# ProPrj___2025-12-10.net
KiCad netlist of a schematic drawn in EasyEDA Pro
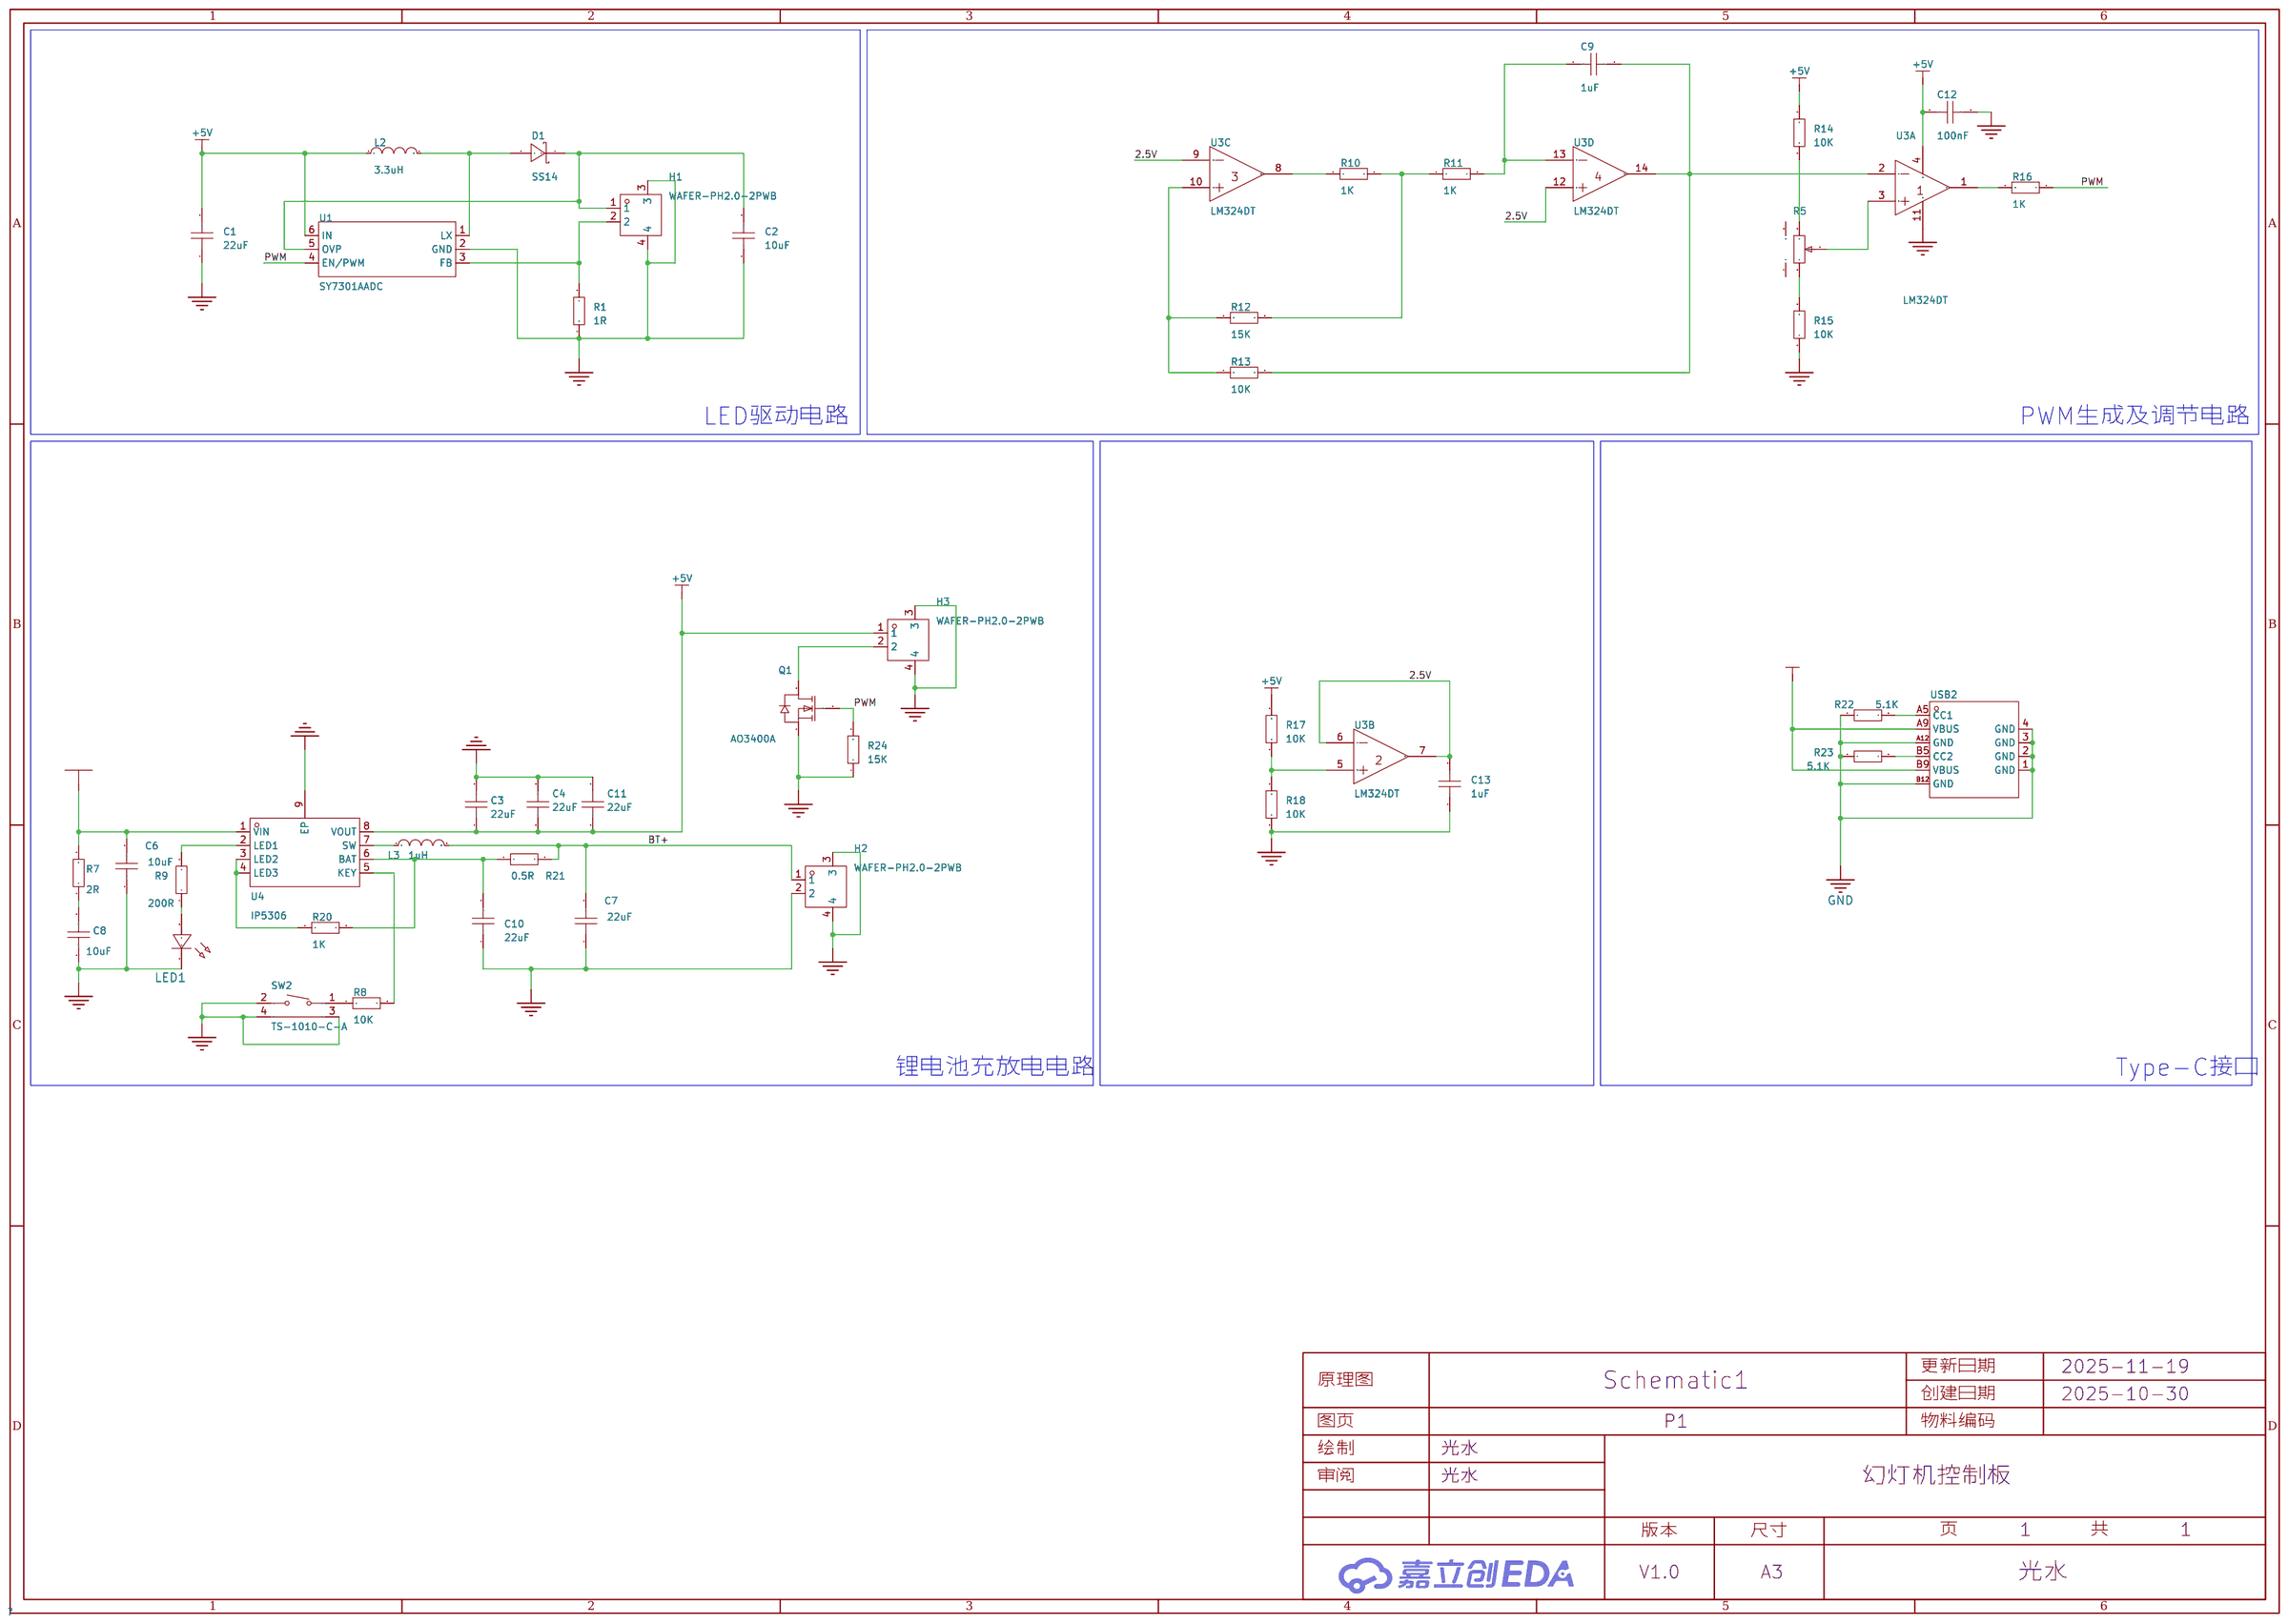
[diagram p0: schematic sheet]

(export (version "E")
  (design (tool "Eeschema 10.0.6"))
  (components
    (comp (ref "C1")
      (value "22uF")
      (footprint "easyedapro:C1206")
      (libsource (lib "easyedapro") (part "CapAcitance"))
    )
    (comp (ref "C2")
      (value "10uF")
      (footprint "easyedapro:C1206")
      (libsource (lib "easyedapro") (part "CapAcitance"))
    )
    (comp (ref "C3")
      (value "22uF")
      (footprint "easyedapro:C0805")
      (description "容值:100nF;精度:±10%;额定电压:50V;温度系数:X7R;")
      (libsource (lib "easyedapro") (part "C1210X7R475K630NT"))
    )
    (comp (ref "C4")
      (value "22uF")
      (footprint "easyedapro:C0805")
      (description "容值:100nF;精度:±10%;额定电压:50V;温度系数:X7R;")
      (libsource (lib "easyedapro") (part "C1210X7R475K630NT"))
    )
    (comp (ref "C6")
      (value "10uF")
      (footprint "easyedapro:C0805")
      (description "容值:100nF;精度:±10%;额定电压:50V;温度系数:X7R;")
      (libsource (lib "easyedapro") (part "C1210X7R475K630NT"))
    )
    (comp (ref "C7")
      (value "22uF")
      (footprint "easyedapro:C0805")
      (description "容值:100nF;精度:±10%;额定电压:50V;温度系数:X7R;")
      (libsource (lib "easyedapro") (part "C1210X7R475K630NT"))
    )
    (comp (ref "C8")
      (value "10uF")
      (footprint "easyedapro:C0805")
      (description "容值:100nF;精度:±10%;额定电压:50V;温度系数:X7R;")
      (libsource (lib "easyedapro") (part "C1210X7R475K630NT"))
    )
    (comp (ref "C9")
      (value "1uF")
      (footprint "easyedapro:C1206")
      (libsource (lib "easyedapro") (part "CapAcitance"))
    )
    (comp (ref "C10")
      (value "22uF")
      (footprint "easyedapro:C1206")
      (libsource (lib "easyedapro") (part "CapAcitance"))
    )
    (comp (ref "C11")
      (value "22uF")
      (footprint "easyedapro:C0805")
      (description "容值:100nF;精度:±10%;额定电压:50V;温度系数:X7R;")
      (libsource (lib "easyedapro") (part "C1210X7R475K630NT"))
    )
    (comp (ref "C12")
      (value "100nF")
      (footprint "easyedapro:C1206")
      (libsource (lib "easyedapro") (part "CapAcitance"))
    )
    (comp (ref "C13")
      (value "1uF")
      (footprint "easyedapro:C1206")
      (libsource (lib "easyedapro") (part "CapAcitance"))
    )
    (comp (ref "D1")
      (value "SS14")
      (footprint "easyedapro:SMA_L4.2-W2.6-LS5.0-RD_1")
      (description "二极管配置:独立式;正向压降(Vf):550mV@1A;直流反向耐压(Vr):40V;整流电流:1A;")
      (fields (field (name "Manufacturer") "MDD(辰达半导体)"))
      (libsource (lib "easyedapro") (part "SS14"))
    )
    (comp (ref "H1")
      (value "WAFER-PH2.0-2PWB")
      (footprint "easyedapro:CONN-SMD_2P-P2.00_XUNPU_WAFER-PH2.0-2PWB")
      (fields (field (name "Manufacturer") "XUNPU(讯普)"))
      (libsource (lib "easyedapro") (part "WAFER-PH2.0-2PWB"))
    )
    (comp (ref "H2")
      (value "WAFER-PH2.0-2PWB")
      (footprint "easyedapro:CONN-SMD_2P-P2.00_XUNPU_WAFER-PH2.0-2PWB")
      (fields (field (name "Manufacturer") "XUNPU(讯普)"))
      (libsource (lib "easyedapro") (part "WAFER-PH2.0-2PWB"))
    )
    (comp (ref "H3")
      (value "WAFER-PH2.0-2PWB")
      (footprint "easyedapro:CONN-SMD_2P-P2.00_XUNPU_WAFER-PH2.0-2PWB")
      (fields (field (name "Manufacturer") "XUNPU(讯普)"))
      (libsource (lib "easyedapro") (part "WAFER-PH2.0-2PWB"))
    )
    (comp (ref "L2")
      (value "3.3uH")
      (footprint "easyedapro:IND-SMD_L7.3-W6.6")
      (description "电感值:3.3uH;精度:±20%;额定电流:-;饱和电流(Isat):9.5A;类型:-;")
      (fields (field (name "Manufacturer Part") "SMMS0630-3R3M") (field (name "Manufacturer") "SXN(顺翔诺)"))
      (libsource (lib "easyedapro") (part "SMMS0630-3R3M"))
    )
    (comp (ref "L3")
      (value "1uH")
      (footprint "easyedapro:IND-SMD_L6.8-W6.8_SMMS0630")
      (description "电感值:1uH;精度:±20%;额定电流:-;饱和电流(Isat):16A;类型:-;")
      (fields (field (name "Manufacturer Part") "SMMS0630-1R0M") (field (name "Manufacturer") "SXN(顺翔诺)"))
      (libsource (lib "easyedapro") (part "SMMS0630-1R0M"))
    )
    (comp (ref "LED1")
      (value "~")
      (footprint "easyedapro:LED0603-RD_BLUE")
      (libsource (lib "easyedapro") (part "LED_R"))
    )
    (comp (ref "Q1")
      (value "AO3400A")
      (footprint "easyedapro:SOT-23-3_L2.9-W1.3-P1.90-LS2.4-BR")
      (description "数量:-;漏源电压(Vdss):30V;连续漏极电流(Id):-;导通电阻(RDS(on)):48mΩ@2.5V;耗散功率(Pd):-;阈值电压(Vgs(th)):1.45V@250uA;")
      (fields (field (name "Manufacturer") "AOS"))
      (libsource (lib "easyedapro") (part "AO3400A"))
    )
    (comp (ref "R1") (value "1R") (footprint "easyedapro:R1210") (libsource (lib "easyedapro") (part "电阻")))
    (comp (ref "R5")
      (value "RV09AF-40-15K-B10K")
      (footprint "easyedapro:RES-ADJ-TH_RV09")
      (libsource (lib "easyedapro") (part "RV09AF-40-15K-B10K"))
    )
    (comp (ref "R7") (value "2R") (footprint "easyedapro:R0603") (libsource (lib "easyedapro") (part "电阻")))
    (comp (ref "R8") (value "10K") (footprint "easyedapro:R1210") (libsource (lib "easyedapro") (part "电阻")))
    (comp (ref "R9") (value "200R") (footprint "easyedapro:R1210") (libsource (lib "easyedapro") (part "电阻")))
    (comp (ref "R10") (value "1K") (footprint "easyedapro:R1210") (libsource (lib "easyedapro") (part "电阻")))
    (comp (ref "R11") (value "1K") (footprint "easyedapro:R1210") (libsource (lib "easyedapro") (part "电阻")))
    (comp (ref "R12") (value "15K") (footprint "easyedapro:R1210") (libsource (lib "easyedapro") (part "电阻")))
    (comp (ref "R13") (value "10K") (footprint "easyedapro:R1210") (libsource (lib "easyedapro") (part "电阻")))
    (comp (ref "R14") (value "10K") (footprint "easyedapro:R1210") (libsource (lib "easyedapro") (part "电阻")))
    (comp (ref "R15") (value "10K") (footprint "easyedapro:R1210") (libsource (lib "easyedapro") (part "电阻")))
    (comp (ref "R16") (value "1K") (footprint "easyedapro:R1210") (libsource (lib "easyedapro") (part "电阻")))
    (comp (ref "R17") (value "10K") (footprint "easyedapro:R1210") (libsource (lib "easyedapro") (part "电阻")))
    (comp (ref "R18") (value "10K") (footprint "easyedapro:R1210") (libsource (lib "easyedapro") (part "电阻")))
    (comp (ref "R20") (value "1K") (footprint "easyedapro:R1210") (libsource (lib "easyedapro") (part "电阻")))
    (comp (ref "R21")
      (value "0.5R")
      (footprint "easyedapro:R1210")
      (libsource (lib "easyedapro") (part "电阻"))
    )
    (comp (ref "R22")
      (value "5.1K")
      (footprint "easyedapro:R0603")
      (libsource (lib "easyedapro") (part "电阻"))
    )
    (comp (ref "R23")
      (value "5.1K")
      (footprint "easyedapro:R0603")
      (libsource (lib "easyedapro") (part "电阻"))
    )
    (comp (ref "R24") (value "15K") (footprint "easyedapro:R1210") (libsource (lib "easyedapro") (part "电阻")))
    (comp (ref "SW2")
      (value "TS-1010-C-A")
      (footprint "easyedapro:KEY-SMD_TX-1010-X-X")
      (fields (field (name "Manufacturer") "XKB Connectivity(中国星坤)"))
      (libsource (lib "easyedapro") (part "TS-1010-C-A"))
    )
    (comp (ref "U1")
      (value "SY7301AADC")
      (footprint "easyedapro:TSOT-23-6_L2.9-W1.6-P0.95-LS2.8-BR")
      (description "开关频率:800kHz~1.2MHz;通道数:1;调光:PWM；模拟;拓扑结构:升压;")
      (fields (field (name "Manufacturer") "Silergy(矽力杰)"))
      (libsource (lib "easyedapro") (part "SY7301AADC"))
    )
    (comp (ref "U3")
      (value "LM324DT")
      (footprint "easyedapro:SOIC-14_L8.7-W3.9-P1.27-LS6.0-BL")
      (description "放大器数:四路;轨到轨:-;增益带宽积(GBP):1.3MHz;输入失调电压(Vos):5mV;压摆率(SR):20V/us;输入偏置电流(Ib):300nA;")
      (fields (field (name "Manufacturer") "ST(意法半导体)"))
      (libsource (lib "easyedapro") (part "LM324DT"))
    )
    (comp (ref "U4")
      (value "IP5306")
      (footprint "easyedapro:ESOP-8_L4.9-W3.9-P1.27-LS6.0-BL-EP")
      (description "工作电压:4.65V~5.5V;最大充电电流:2.1A;电池类型:锂电池;电池节数:1;")
      (fields (field (name "Manufacturer") "INJOINIC(英集芯)"))
      (libsource (lib "easyedapro") (part "IP5306"))
    )
    (comp (ref "USB2")
      (value "~")
      (footprint "easyedapro:usb-c-smd_typec-250d-bcp6")
      (description "连接器类型:Type-C;标准:USB 3.1;公母:母座;触点数量:6;端口数量:1;安装方式:卧贴;额定电流 - 电源:3A;工作温度范围:-25~+85;焊接温度(最大值):260;")
      (fields (field (name "Manufacturer Part") "TYPEC-250D-BCP6") (field (name "Manufacturer") "XUNPU(讯普)"))
      (libsource (lib "easyedapro") (part "typec-250d-bcp6"))
    )
  )
  (nets
    (net (code "1") (name "+5V") (class "Default")
      (node (ref "C1") (pin "2") (pinfunction "2_2") (pintype "input"))
      (node (ref "C11") (pin "1") (pinfunction "1_1") (pintype "input"))
      (node (ref "C12") (pin "1") (pinfunction "1_1") (pintype "input"))
      (node (ref "C3") (pin "1") (pinfunction "1_1") (pintype "input"))
      (node (ref "C4") (pin "1") (pinfunction "1_1") (pintype "input"))
      (node (ref "H3") (pin "1") (pinfunction "1_1") (pintype "unspecified"))
      (node (ref "L2") (pin "1") (pinfunction "1_1") (pintype "unspecified"))
      (node (ref "R14") (pin "2") (pinfunction "2_2") (pintype "input"))
      (node (ref "R17") (pin "2") (pinfunction "2_2") (pintype "input"))
      (node (ref "U1") (pin "6") (pinfunction "IN_6") (pintype "unspecified"))
      (node (ref "U3") (pin "4") (pinfunction "VCC+_4") (pintype "unspecified"))
      (node (ref "U4") (pin "8") (pinfunction "VOUT_8") (pintype "unspecified"))
    )
    (net (code "2") (name "/2.5V") (class "Default")
      (node (ref "C13") (pin "2") (pinfunction "2_2") (pintype "input"))
      (node (ref "U3") (pin "12") (pinfunction "IN4+_12") (pintype "unspecified"))
      (node (ref "U3") (pin "6") (pinfunction "IN2-_6") (pintype "unspecified"))
      (node (ref "U3") (pin "7") (pinfunction "OUT2_7") (pintype "unspecified"))
      (node (ref "U3") (pin "9") (pinfunction "IN3-_9") (pintype "unspecified"))
    )
    (net (code "3") (name "/BT+") (class "Default")
      (node (ref "C7") (pin "2") (pinfunction "2_2") (pintype "input"))
      (node (ref "H2") (pin "1") (pinfunction "1_1") (pintype "unspecified"))
      (node (ref "L3") (pin "2") (pinfunction "2_2") (pintype "unspecified"))
      (node (ref "R21") (pin "2") (pinfunction "2_2") (pintype "input"))
    )
    (net (code "4") (name "/PWM") (class "Default")
      (node (ref "Q1") (pin "1") (pinfunction "G_1") (pintype "unspecified"))
      (node (ref "R16") (pin "2") (pinfunction "2_2") (pintype "input"))
      (node (ref "R24") (pin "2") (pinfunction "2_2") (pintype "input"))
      (node (ref "U1") (pin "4") (pinfunction "EN/PWM_4") (pintype "unspecified"))
    )
    (net (code "5") (name "GND") (class "Default")
      (node (ref "C1") (pin "1") (pinfunction "1_1") (pintype "input"))
      (node (ref "C10") (pin "1") (pinfunction "1_1") (pintype "input"))
      (node (ref "C11") (pin "2") (pinfunction "2_2") (pintype "input"))
      (node (ref "C12") (pin "2") (pinfunction "2_2") (pintype "input"))
      (node (ref "C13") (pin "1") (pinfunction "1_1") (pintype "input"))
      (node (ref "C2") (pin "1") (pinfunction "1_1") (pintype "input"))
      (node (ref "C3") (pin "2") (pinfunction "2_2") (pintype "input"))
      (node (ref "C4") (pin "2") (pinfunction "2_2") (pintype "input"))
      (node (ref "C6") (pin "1") (pinfunction "1_1") (pintype "input"))
      (node (ref "C7") (pin "1") (pinfunction "1_1") (pintype "input"))
      (node (ref "C8") (pin "1") (pinfunction "1_1") (pintype "input"))
      (node (ref "H1") (pin "3") (pinfunction "3_3") (pintype "unspecified"))
      (node (ref "H1") (pin "4") (pinfunction "4_4") (pintype "unspecified"))
      (node (ref "H2") (pin "2") (pinfunction "2_2") (pintype "unspecified"))
      (node (ref "H2") (pin "3") (pinfunction "3_3") (pintype "unspecified"))
      (node (ref "H2") (pin "4") (pinfunction "4_4") (pintype "unspecified"))
      (node (ref "H3") (pin "3") (pinfunction "3_3") (pintype "unspecified"))
      (node (ref "H3") (pin "4") (pinfunction "4_4") (pintype "unspecified"))
      (node (ref "LED1") (pin "1") (pinfunction "C_1") (pintype "input"))
      (node (ref "Q1") (pin "2") (pinfunction "S_2") (pintype "unspecified"))
      (node (ref "R1") (pin "1") (pinfunction "1_1") (pintype "input"))
      (node (ref "R15") (pin "1") (pinfunction "1_1") (pintype "input"))
      (node (ref "R18") (pin "1") (pinfunction "1_1") (pintype "input"))
      (node (ref "R22") (pin "1") (pinfunction "1_1") (pintype "input"))
      (node (ref "R23") (pin "2") (pinfunction "2_2") (pintype "input"))
      (node (ref "R24") (pin "1") (pinfunction "1_1") (pintype "input"))
      (node (ref "SW2") (pin "2") (pinfunction "2_2") (pintype "input"))
      (node (ref "SW2") (pin "3") (pinfunction "3_3") (pintype "input"))
      (node (ref "SW2") (pin "4") (pinfunction "4_4") (pintype "input"))
      (node (ref "U1") (pin "2") (pinfunction "GND_2") (pintype "unspecified"))
      (node (ref "U3") (pin "11") (pinfunction "VCC-_11") (pintype "unspecified"))
      (node (ref "U4") (pin "9") (pinfunction "EP_9") (pintype "unspecified"))
      (node (ref "USB2") (pin "1") (pinfunction "GND_1") (pintype "input"))
      (node (ref "USB2") (pin "2") (pinfunction "GND_2") (pintype "input"))
      (node (ref "USB2") (pin "3") (pinfunction "GND_3") (pintype "input"))
      (node (ref "USB2") (pin "4") (pinfunction "GND_4") (pintype "input"))
      (node (ref "USB2") (pin "A12") (pinfunction "GND_A12") (pintype "input"))
      (node (ref "USB2") (pin "B12") (pinfunction "GND_B12") (pintype "input"))
    )
    (net (code "6") (name "Net-(C8-Pad2)") (class "Default")
      (node (ref "C8") (pin "2") (pinfunction "2_2") (pintype "input"))
      (node (ref "R7") (pin "1") (pinfunction "1_1") (pintype "input"))
    )
    (net (code "7") (name "Net-(D1-A)") (class "Default")
      (node (ref "D1") (pin "2") (pinfunction "A_2") (pintype "unspecified"))
      (node (ref "L2") (pin "2") (pinfunction "2_2") (pintype "unspecified"))
      (node (ref "U1") (pin "1") (pinfunction "LX_1") (pintype "unspecified"))
    )
    (net (code "8") (name "Net-(D1-K)") (class "Default")
      (node (ref "C2") (pin "2") (pinfunction "2_2") (pintype "input"))
      (node (ref "D1") (pin "1") (pinfunction "K_1") (pintype "unspecified"))
      (node (ref "H1") (pin "1") (pinfunction "1_1") (pintype "unspecified"))
      (node (ref "U1") (pin "5") (pinfunction "OVP_5") (pintype "unspecified"))
    )
    (net (code "9") (name "Net-(LED1-A)") (class "Default")
      (node (ref "LED1") (pin "2") (pinfunction "A_2") (pintype "input"))
      (node (ref "R9") (pin "1") (pinfunction "1_1") (pintype "input"))
    )
    (net (code "10") (name "Net-(Q1-D)") (class "Default")
      (node (ref "H3") (pin "2") (pinfunction "2_2") (pintype "unspecified"))
      (node (ref "Q1") (pin "3") (pinfunction "D_3") (pintype "unspecified"))
    )
    (net (code "11") (name "Net-(R8-Pad1)") (class "Default")
      (node (ref "R8") (pin "1") (pinfunction "1_1") (pintype "input"))
      (node (ref "SW2") (pin "1") (pinfunction "1_1") (pintype "input"))
    )
    (net (code "12") (name "Net-(R10-Pad2)") (class "Default")
      (node (ref "R10") (pin "2") (pinfunction "2_2") (pintype "input"))
      (node (ref "R11") (pin "1") (pinfunction "1_1") (pintype "input"))
      (node (ref "R12") (pin "2") (pinfunction "2_2") (pintype "input"))
    )
    (net (code "13") (name "Net-(R14-Pad1)") (class "Default")
      (node (ref "R14") (pin "1") (pinfunction "1_1") (pintype "input"))
      (node (ref "R5") (pin "3") (pinfunction "3_3") (pintype "input"))
    )
    (net (code "14") (name "Net-(R15-Pad2)") (class "Default")
      (node (ref "R15") (pin "2") (pinfunction "2_2") (pintype "input"))
      (node (ref "R5") (pin "1") (pinfunction "1_1") (pintype "input"))
    )
    (net (code "15") (name "Net-(U1-FB)") (class "Default")
      (node (ref "H1") (pin "2") (pinfunction "2_2") (pintype "unspecified"))
      (node (ref "R1") (pin "2") (pinfunction "2_2") (pintype "input"))
      (node (ref "U1") (pin "3") (pinfunction "FB_3") (pintype "unspecified"))
    )
    (net (code "16") (name "Net-(U3A-IN1+)") (class "Default")
      (node (ref "R5") (pin "2") (pinfunction "2_2") (pintype "input"))
      (node (ref "U3") (pin "3") (pinfunction "IN1+_3") (pintype "unspecified"))
    )
    (net (code "17") (name "Net-(U3A-IN1-)") (class "Default")
      (node (ref "C9") (pin "2") (pinfunction "2_2") (pintype "input"))
      (node (ref "R13") (pin "2") (pinfunction "2_2") (pintype "input"))
      (node (ref "U3") (pin "14") (pinfunction "OUT4_14") (pintype "unspecified"))
      (node (ref "U3") (pin "2") (pinfunction "IN1-_2") (pintype "unspecified"))
    )
    (net (code "18") (name "Net-(U3A-OUT1)") (class "Default")
      (node (ref "R16") (pin "1") (pinfunction "1_1") (pintype "input"))
      (node (ref "U3") (pin "1") (pinfunction "OUT1_1") (pintype "unspecified"))
    )
    (net (code "19") (name "Net-(U3B-IN2+)") (class "Default")
      (node (ref "R17") (pin "1") (pinfunction "1_1") (pintype "input"))
      (node (ref "R18") (pin "2") (pinfunction "2_2") (pintype "input"))
      (node (ref "U3") (pin "5") (pinfunction "IN2+_5") (pintype "unspecified"))
    )
    (net (code "20") (name "Net-(U3C-IN3+)") (class "Default")
      (node (ref "R12") (pin "1") (pinfunction "1_1") (pintype "input"))
      (node (ref "R13") (pin "1") (pinfunction "1_1") (pintype "input"))
      (node (ref "U3") (pin "10") (pinfunction "IN3+_10") (pintype "unspecified"))
    )
    (net (code "21") (name "Net-(U3C-OUT3)") (class "Default")
      (node (ref "R10") (pin "1") (pinfunction "1_1") (pintype "input"))
      (node (ref "U3") (pin "8") (pinfunction "OUT3_8") (pintype "unspecified"))
    )
    (net (code "22") (name "Net-(U3D-IN4-)") (class "Default")
      (node (ref "C9") (pin "1") (pinfunction "1_1") (pintype "input"))
      (node (ref "R11") (pin "2") (pinfunction "2_2") (pintype "input"))
      (node (ref "U3") (pin "13") (pinfunction "IN4-_13") (pintype "unspecified"))
    )
    (net (code "23") (name "Net-(U4-BAT)") (class "Default")
      (node (ref "C10") (pin "2") (pinfunction "2_2") (pintype "input"))
      (node (ref "R20") (pin "2") (pinfunction "2_2") (pintype "input"))
      (node (ref "R21") (pin "1") (pinfunction "1_1") (pintype "input"))
      (node (ref "U4") (pin "6") (pinfunction "BAT_6") (pintype "unspecified"))
    )
    (net (code "24") (name "Net-(U4-KEY)") (class "Default")
      (node (ref "R8") (pin "2") (pinfunction "2_2") (pintype "input"))
      (node (ref "U4") (pin "5") (pinfunction "KEY_5") (pintype "unspecified"))
    )
    (net (code "25") (name "Net-(U4-LED1)") (class "Default")
      (node (ref "R9") (pin "2") (pinfunction "2_2") (pintype "input"))
      (node (ref "U4") (pin "2") (pinfunction "LED1_2") (pintype "unspecified"))
    )
    (net (code "26") (name "Net-(U4-LED2)") (class "Default")
      (node (ref "R20") (pin "1") (pinfunction "1_1") (pintype "input"))
      (node (ref "U4") (pin "3") (pinfunction "LED2_3") (pintype "unspecified"))
      (node (ref "U4") (pin "4") (pinfunction "LED3_4") (pintype "unspecified"))
    )
    (net (code "27") (name "Net-(U4-SW)") (class "Default")
      (node (ref "L3") (pin "1") (pinfunction "1_1") (pintype "unspecified"))
      (node (ref "U4") (pin "7") (pinfunction "SW_7") (pintype "unspecified"))
    )
    (net (code "28") (name "Net-(USB2-CC1)") (class "Default")
      (node (ref "R22") (pin "2") (pinfunction "2_2") (pintype "input"))
      (node (ref "USB2") (pin "A5") (pinfunction "CC1_A5") (pintype "input"))
    )
    (net (code "29") (name "Net-(USB2-CC2)") (class "Default")
      (node (ref "R23") (pin "1") (pinfunction "1_1") (pintype "input"))
      (node (ref "USB2") (pin "B5") (pinfunction "CC2_B5") (pintype "input"))
    )
    (net (code "30") (name "VUSB") (class "Default")
      (node (ref "C6") (pin "2") (pinfunction "2_2") (pintype "input"))
      (node (ref "R7") (pin "2") (pinfunction "2_2") (pintype "input"))
      (node (ref "U4") (pin "1") (pinfunction "VIN_1") (pintype "unspecified"))
      (node (ref "USB2") (pin "A9") (pinfunction "VBUS_A9") (pintype "input"))
      (node (ref "USB2") (pin "B9") (pinfunction "VBUS_B9") (pintype "input"))
    )
    (net (code "31") (name "unconnected-(R5-Pad4)") (class "Default")
      (node (ref "R5") (pin "4") (pinfunction "4_4") (pintype "input"))
    )
    (net (code "32") (name "unconnected-(R5-Pad5)") (class "Default")
      (node (ref "R5") (pin "5") (pinfunction "5_5") (pintype "input"))
    )
  )
)
